# Sheet1_-_mos.net
KiCad netlist of a schematic drawn in Altium Designer
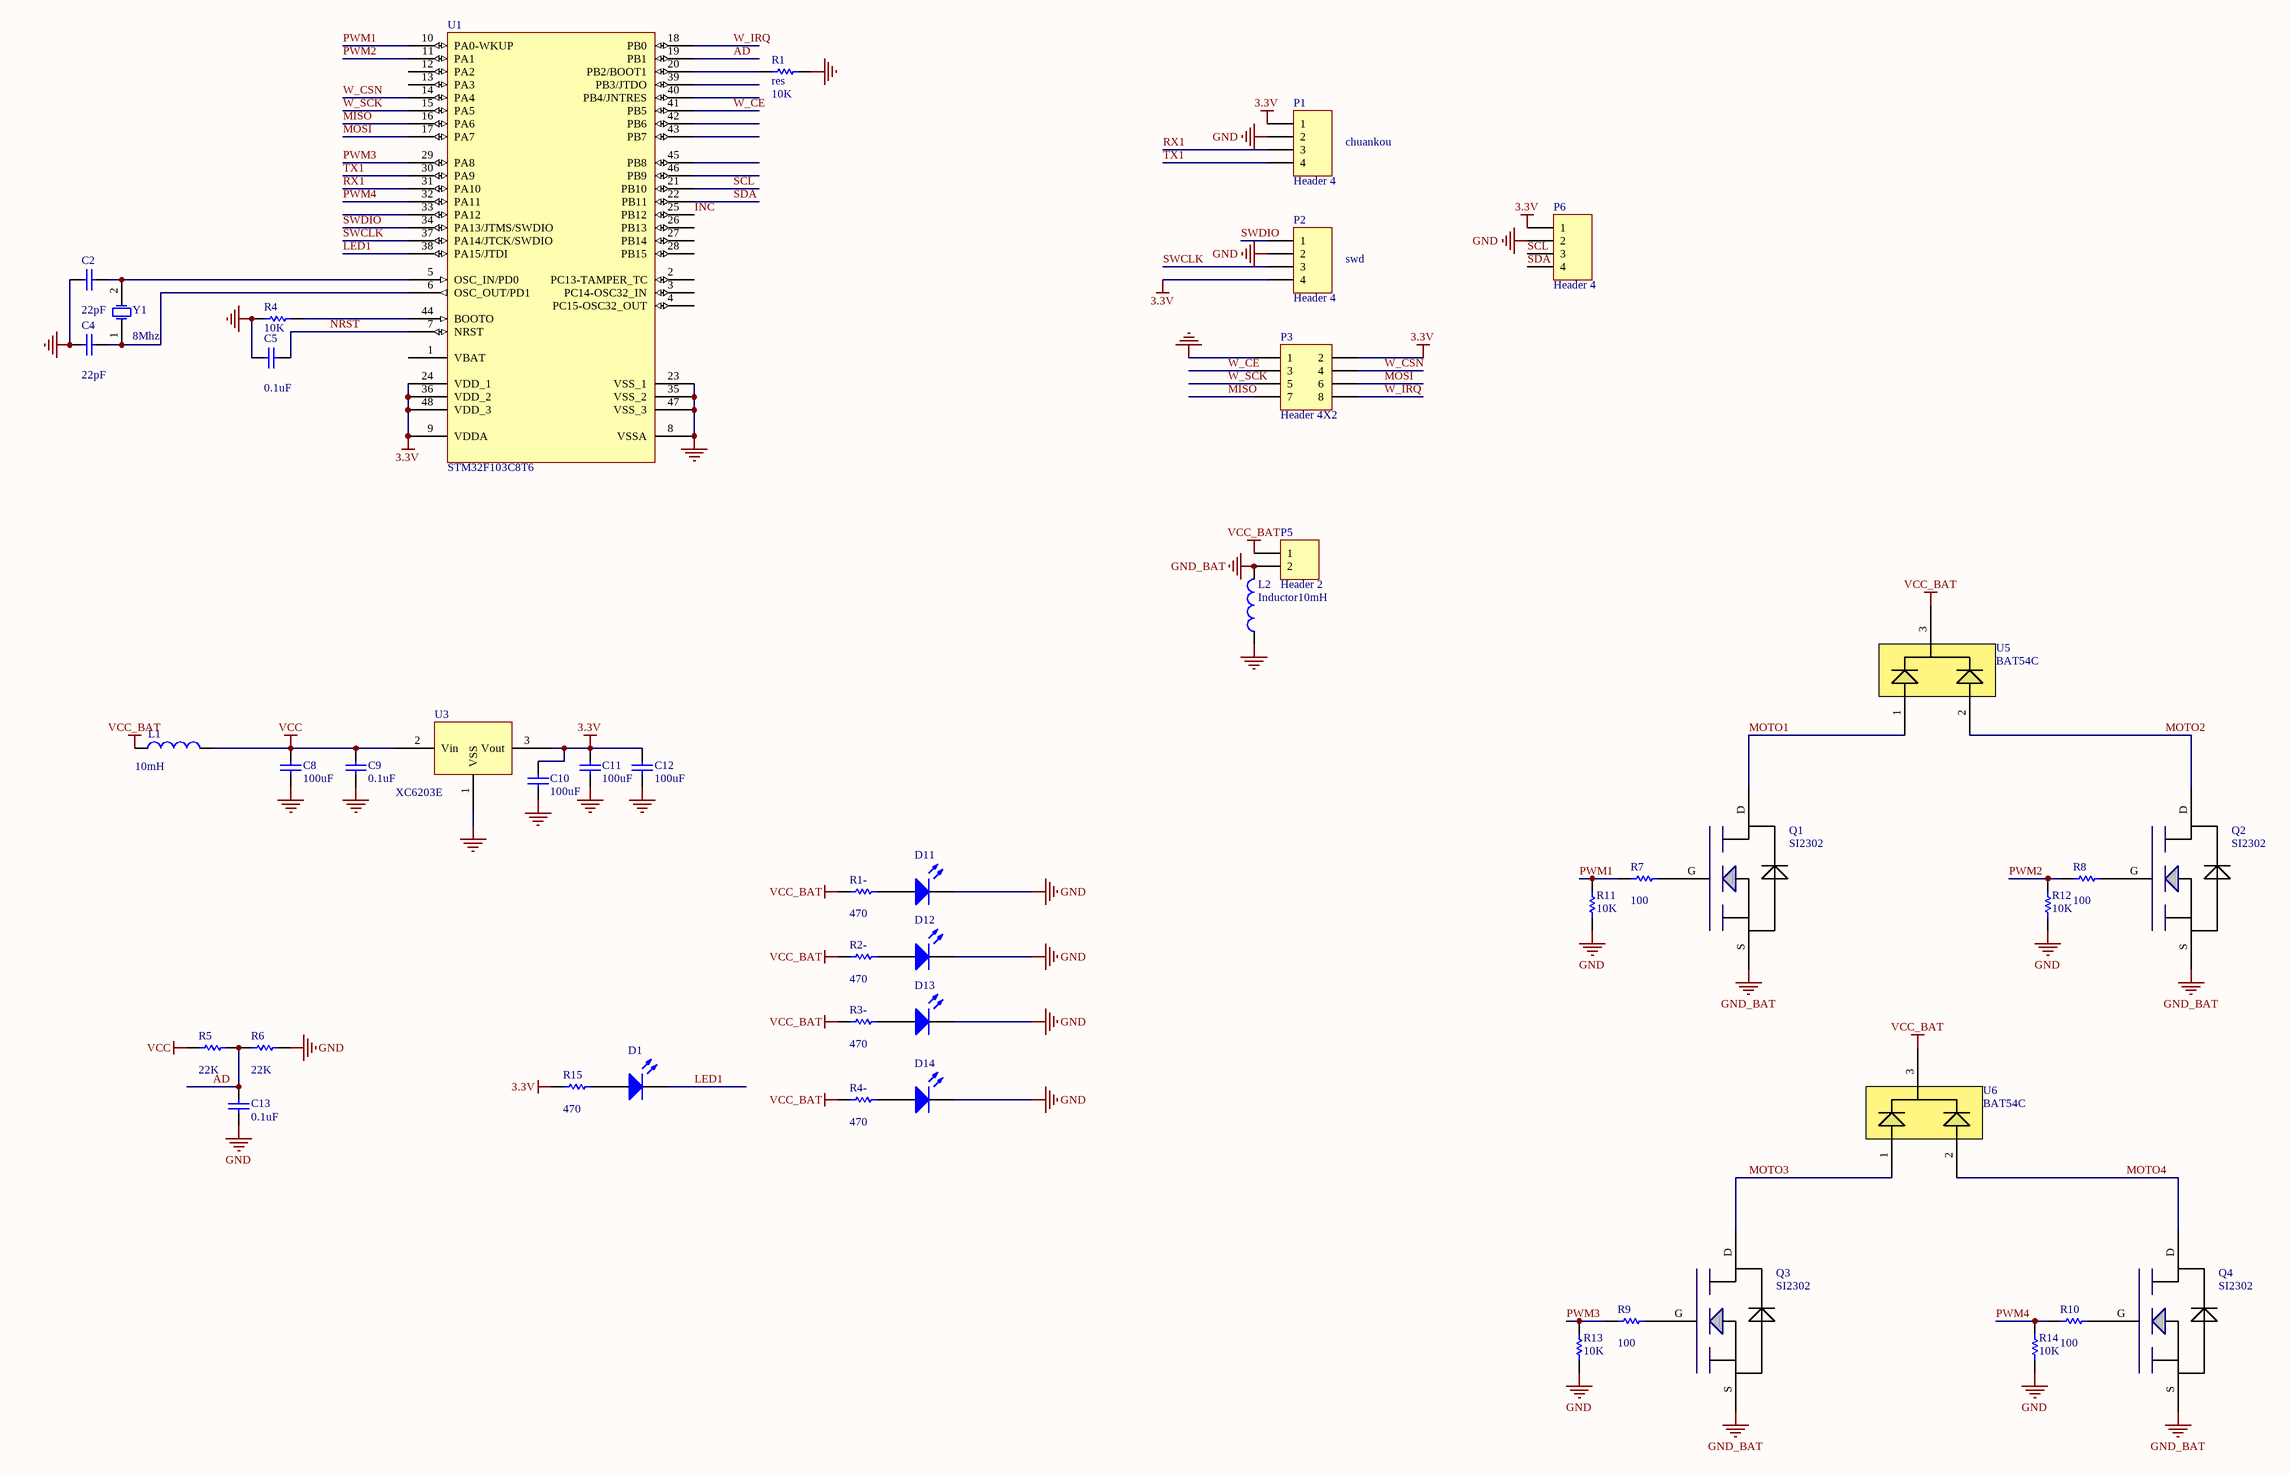
[diagram p0: Sheet1 - 修改mos管.SchDoc]

(export (version "E")
  (design (tool "Eeschema 10.0.6"))
  (components
    (comp (ref "C2")
      (value "22pF")
      (footprint "0603")
      (fields (field (name "Comment") "cap"))
      (libsource (lib "bai") (part "cap"))
    )
    (comp (ref "C4")
      (value "22pF")
      (footprint "0603")
      (fields (field (name "Comment") "cap"))
      (libsource (lib "bai") (part "cap"))
    )
    (comp (ref "C5")
      (value "0.1uF")
      (footprint "0603")
      (fields (field (name "Comment") "cap"))
      (libsource (lib "bai") (part "cap"))
    )
    (comp (ref "C8")
      (value "100uF")
      (footprint "0603")
      (fields (field (name "Comment") "cap"))
      (libsource (lib "bai") (part "cap"))
    )
    (comp (ref "C9")
      (value "0.1uF")
      (footprint "0603")
      (fields (field (name "Comment") "cap"))
      (libsource (lib "bai") (part "cap"))
    )
    (comp (ref "C10")
      (value "100uF")
      (footprint "0603")
      (fields (field (name "Comment") "cap"))
      (libsource (lib "bai") (part "cap"))
    )
    (comp (ref "C11")
      (value "100uF")
      (footprint "0603")
      (fields (field (name "Comment") "cap"))
      (libsource (lib "bai") (part "cap"))
    )
    (comp (ref "C12")
      (value "100uF")
      (footprint "0603")
      (fields (field (name "Comment") "cap"))
      (libsource (lib "bai") (part "cap"))
    )
    (comp (ref "C13")
      (value "0.1uF")
      (footprint "0603")
      (fields (field (name "Comment") "cap"))
      (libsource (lib "bai") (part "cap"))
    )
    (comp (ref "D1")
      (value "LED0")
      (footprint "0805")
      (description "Typical INFRARED GaAs LED")
      (fields (field (name "PUBLISHER") "Altium Limited"))
      (libsource (lib "Miscellaneous Devices") (part "LED0"))
    )
    (comp (ref "D11")
      (value "LED0")
      (footprint "0603c")
      (description "Typical INFRARED GaAs LED")
      (fields (field (name "PUBLISHER") "Altium Limited"))
      (libsource (lib "Miscellaneous Devices") (part "LED0"))
    )
    (comp (ref "D12")
      (value "LED0")
      (footprint "0603c")
      (description "Typical INFRARED GaAs LED")
      (fields (field (name "PUBLISHER") "Altium Limited"))
      (libsource (lib "Miscellaneous Devices") (part "LED0"))
    )
    (comp (ref "D13")
      (value "LED0")
      (footprint "0603c")
      (description "Typical INFRARED GaAs LED")
      (fields (field (name "PUBLISHER") "Altium Limited"))
      (libsource (lib "Miscellaneous Devices") (part "LED0"))
    )
    (comp (ref "D14")
      (value "LED0")
      (footprint "0603c")
      (description "Typical INFRARED GaAs LED")
      (fields (field (name "PUBLISHER") "Altium Limited"))
      (libsource (lib "Miscellaneous Devices") (part "LED0"))
    )
    (comp (ref "L1")
      (value "10mH")
      (footprint "0805")
      (fields (field (name "Comment") "Inductor"))
      (libsource (lib "bai") (part "Inductor"))
    )
    (comp (ref "L2") (value "Inductor10mH") (footprint "0805") (libsource (lib "bai") (part "Inductor")))
    (comp (ref "P1")
      (value "Header 4")
      (footprint "HDR1X4")
      (description "Header, 4-Pin")
      (fields (field (name "PUBLISHER") "Altium Limited"))
      (libsource (lib "Miscellaneous Connectors") (part "Header 4"))
    )
    (comp (ref "P2")
      (value "Header 4")
      (footprint "HDR1X4")
      (description "Header, 4-Pin")
      (fields (field (name "PUBLISHER") "Altium Limited"))
      (libsource (lib "Miscellaneous Connectors") (part "Header 4"))
    )
    (comp (ref "P3")
      (value "Header 4X2")
      (footprint "HDR2X4")
      (description "Header, 4-Pin, Dual row")
      (fields (field (name "PUBLISHER") "Altium Limited"))
      (libsource (lib "Miscellaneous Connectors") (part "Header 4X2"))
    )
    (comp (ref "P5")
      (value "Header 2")
      (footprint "HDR1X2")
      (description "Header, 2-Pin")
      (fields (field (name "PUBLISHER") "Altium Limited"))
      (libsource (lib "Miscellaneous Connectors") (part "Header 2"))
    )
    (comp (ref "P6")
      (value "Header 4")
      (footprint "HDR1X4")
      (description "Header, 4-Pin")
      (fields (field (name "PUBLISHER") "Altium Limited"))
      (libsource (lib "Miscellaneous Connectors") (part "Header 4"))
    )
    (comp (ref "Q1") (value "SI2302") (footprint "SOT-23") (libsource (lib "bai") (part "SI2302")))
    (comp (ref "Q2") (value "SI2302") (footprint "SOT-23") (libsource (lib "bai") (part "SI2302")))
    (comp (ref "Q3") (value "SI2302") (footprint "SOT-23") (libsource (lib "bai") (part "SI2302")))
    (comp (ref "Q4") (value "SI2302") (footprint "SOT-23") (libsource (lib "bai") (part "SI2302")))
    (comp (ref "R1")
      (value "res")
      (footprint "0603")
      (fields (field (name "RES") "10K"))
      (libsource (lib "bai") (part "res"))
    )
    (comp (ref "R1-")
      (value "res")
      (footprint "0603c")
      (fields (field (name "RES") "470"))
      (libsource (lib "bai") (part "res"))
    )
    (comp (ref "R2-")
      (value "res")
      (footprint "0603c")
      (fields (field (name "RES") "470"))
      (libsource (lib "bai") (part "res"))
    )
    (comp (ref "R3-")
      (value "res")
      (footprint "0603c")
      (fields (field (name "RES") "470"))
      (libsource (lib "bai") (part "res"))
    )
    (comp (ref "R4")
      (value "res")
      (footprint "0603")
      (fields (field (name "RES") "10K"))
      (libsource (lib "bai") (part "res"))
    )
    (comp (ref "R4-")
      (value "res")
      (footprint "0603c")
      (fields (field (name "RES") "470"))
      (libsource (lib "bai") (part "res"))
    )
    (comp (ref "R5")
      (value "res")
      (footprint "0603")
      (fields (field (name "RES") "22K"))
      (libsource (lib "bai") (part "res"))
    )
    (comp (ref "R6")
      (value "res")
      (footprint "0603")
      (fields (field (name "RES") "22K"))
      (libsource (lib "bai") (part "res"))
    )
    (comp (ref "R7")
      (value "res")
      (footprint "0603")
      (fields (field (name "RES") "100"))
      (libsource (lib "bai") (part "res"))
    )
    (comp (ref "R8")
      (value "res")
      (footprint "0603")
      (fields (field (name "RES") "100"))
      (libsource (lib "bai") (part "res"))
    )
    (comp (ref "R9")
      (value "res")
      (footprint "0603")
      (fields (field (name "RES") "100"))
      (libsource (lib "bai") (part "res"))
    )
    (comp (ref "R10")
      (value "res")
      (footprint "0603")
      (fields (field (name "RES") "100"))
      (libsource (lib "bai") (part "res"))
    )
    (comp (ref "R11")
      (value "res")
      (footprint "0603")
      (fields (field (name "RES") "10K"))
      (libsource (lib "bai") (part "res"))
    )
    (comp (ref "R12")
      (value "res")
      (footprint "0603")
      (fields (field (name "RES") "10K"))
      (libsource (lib "bai") (part "res"))
    )
    (comp (ref "R13")
      (value "res")
      (footprint "0603")
      (fields (field (name "RES") "10K"))
      (libsource (lib "bai") (part "res"))
    )
    (comp (ref "R14")
      (value "res")
      (footprint "0603")
      (fields (field (name "RES") "10K"))
      (libsource (lib "bai") (part "res"))
    )
    (comp (ref "R15")
      (value "res")
      (footprint "0603")
      (fields (field (name "RES") "470"))
      (libsource (lib "bai") (part "res"))
    )
    (comp (ref "U1")
      (value "STM32F103C8T6")
      (footprint "LQFP48S")
      (libsource (lib "bai") (part "STM32F103C8T6"))
    )
    (comp (ref "U3") (value "XC6203E") (footprint "SOT-89") (libsource (lib "文哥做的") (part "XC6203")))
    (comp (ref "U5") (value "BAT54C") (footprint "SOT-23") (libsource (lib "bai") (part "BAT54C")))
    (comp (ref "U6") (value "BAT54C") (footprint "SOT-23") (libsource (lib "bai") (part "BAT54C")))
    (comp (ref "Y1")
      (value "5032xtal")
      (footprint "XTAL")
      (fields (field (name "ALTIUM_UNNAMED_1") "8Mhz"))
      (libsource (lib "bai") (part "5032xtal"))
    )
  )
  (nets
    (net (code "1") (name "/AD") (class "Default")
      (node (ref "C13") (pin "2") (pinfunction "2_2") (pintype "passive"))
      (node (ref "R5") (pin "2") (pinfunction "2_2") (pintype "passive"))
      (node (ref "R6") (pin "1") (pinfunction "1_1") (pintype "passive"))
      (node (ref "U1") (pin "19") (pinfunction "PB1_19") (pintype "bidirectional"))
    )
    (net (code "2") (name "/INC") (class "Default")
      (node (ref "U1") (pin "25") (pinfunction "PB12_25") (pintype "bidirectional"))
    )
    (net (code "3") (name "/LED1") (class "Default")
      (node (ref "D1") (pin "2") (pinfunction "K_2") (pintype "passive"))
      (node (ref "U1") (pin "38") (pinfunction "PA15/JTDI_38") (pintype "bidirectional"))
    )
    (net (code "4") (name "/MISO") (class "Default")
      (node (ref "P3") (pin "7") (pinfunction "7_7") (pintype "passive"))
      (node (ref "U1") (pin "16") (pinfunction "PA6_16") (pintype "bidirectional"))
    )
    (net (code "5") (name "/MOSI") (class "Default")
      (node (ref "P3") (pin "6") (pinfunction "6_6") (pintype "passive"))
      (node (ref "U1") (pin "17") (pinfunction "PA7_17") (pintype "bidirectional"))
    )
    (net (code "6") (name "/MOTO1") (class "Default")
      (node (ref "Q1") (pin "D") (pinfunction "3_D") (pintype "passive"))
      (node (ref "U5") (pin "1") (pinfunction "4_1") (pintype "passive"))
    )
    (net (code "7") (name "/MOTO2") (class "Default")
      (node (ref "Q2") (pin "D") (pinfunction "3_D") (pintype "passive"))
      (node (ref "U5") (pin "2") (pinfunction "5_2") (pintype "passive"))
    )
    (net (code "8") (name "/MOTO3") (class "Default")
      (node (ref "Q3") (pin "D") (pinfunction "3_D") (pintype "passive"))
      (node (ref "U6") (pin "1") (pinfunction "4_1") (pintype "passive"))
    )
    (net (code "9") (name "/MOTO4") (class "Default")
      (node (ref "Q4") (pin "D") (pinfunction "3_D") (pintype "passive"))
      (node (ref "U6") (pin "2") (pinfunction "5_2") (pintype "passive"))
    )
    (net (code "10") (name "/NRST") (class "Default")
      (node (ref "C5") (pin "2") (pinfunction "2_2") (pintype "passive"))
      (node (ref "U1") (pin "7") (pinfunction "NRST_7") (pintype "bidirectional"))
    )
    (net (code "11") (name "/PWM1") (class "Default")
      (node (ref "R11") (pin "2") (pinfunction "2_2") (pintype "passive"))
      (node (ref "R7") (pin "1") (pinfunction "1_1") (pintype "passive"))
      (node (ref "U1") (pin "10") (pinfunction "PA0-WKUP_10") (pintype "bidirectional"))
    )
    (net (code "12") (name "/PWM2") (class "Default")
      (node (ref "R12") (pin "2") (pinfunction "2_2") (pintype "passive"))
      (node (ref "R8") (pin "1") (pinfunction "1_1") (pintype "passive"))
      (node (ref "U1") (pin "11") (pinfunction "PA1_11") (pintype "bidirectional"))
    )
    (net (code "13") (name "/PWM3") (class "Default")
      (node (ref "R13") (pin "2") (pinfunction "2_2") (pintype "passive"))
      (node (ref "R9") (pin "1") (pinfunction "1_1") (pintype "passive"))
      (node (ref "U1") (pin "29") (pinfunction "PA8_29") (pintype "bidirectional"))
    )
    (net (code "14") (name "/PWM4") (class "Default")
      (node (ref "R10") (pin "1") (pinfunction "1_1") (pintype "passive"))
      (node (ref "R14") (pin "2") (pinfunction "2_2") (pintype "passive"))
      (node (ref "U1") (pin "32") (pinfunction "PA11_32") (pintype "bidirectional"))
    )
    (net (code "15") (name "/RX1") (class "Default")
      (node (ref "P1") (pin "3") (pinfunction "3_3") (pintype "passive"))
      (node (ref "U1") (pin "31") (pinfunction "PA10_31") (pintype "bidirectional"))
    )
    (net (code "16") (name "/SCL") (class "Default")
      (node (ref "P6") (pin "3") (pinfunction "3_3") (pintype "passive"))
      (node (ref "U1") (pin "21") (pinfunction "PB10_21") (pintype "bidirectional"))
    )
    (net (code "17") (name "/SDA") (class "Default")
      (node (ref "P6") (pin "4") (pinfunction "4_4") (pintype "passive"))
      (node (ref "U1") (pin "22") (pinfunction "PB11_22") (pintype "bidirectional"))
    )
    (net (code "18") (name "/SWCLK") (class "Default")
      (node (ref "P2") (pin "3") (pinfunction "3_3") (pintype "passive"))
      (node (ref "U1") (pin "37") (pinfunction "PA14/JTCK/SWDIO_37") (pintype "bidirectional"))
    )
    (net (code "19") (name "/SWDIO") (class "Default")
      (node (ref "P2") (pin "1") (pinfunction "1_1") (pintype "passive"))
      (node (ref "U1") (pin "34") (pinfunction "PA13/JTMS/SWDIO_34") (pintype "bidirectional"))
    )
    (net (code "20") (name "/TX1") (class "Default")
      (node (ref "P1") (pin "4") (pinfunction "4_4") (pintype "passive"))
      (node (ref "U1") (pin "30") (pinfunction "PA9_30") (pintype "bidirectional"))
    )
    (net (code "21") (name "/W_CE") (class "Default")
      (node (ref "P3") (pin "3") (pinfunction "3_3") (pintype "passive"))
      (node (ref "U1") (pin "41") (pinfunction "PB5_41") (pintype "bidirectional"))
    )
    (net (code "22") (name "/W_CSN") (class "Default")
      (node (ref "P3") (pin "4") (pinfunction "4_4") (pintype "passive"))
      (node (ref "U1") (pin "14") (pinfunction "PA4_14") (pintype "bidirectional"))
    )
    (net (code "23") (name "/W_IRQ") (class "Default")
      (node (ref "P3") (pin "8") (pinfunction "8_8") (pintype "passive"))
      (node (ref "U1") (pin "18") (pinfunction "PB0_18") (pintype "bidirectional"))
    )
    (net (code "24") (name "/W_SCK") (class "Default")
      (node (ref "P3") (pin "5") (pinfunction "5_5") (pintype "passive"))
      (node (ref "U1") (pin "15") (pinfunction "PA5_15") (pintype "bidirectional"))
    )
    (net (code "25") (name "3.3V") (class "Default")
      (node (ref "C10") (pin "2") (pinfunction "2_2") (pintype "passive"))
      (node (ref "C11") (pin "2") (pinfunction "2_2") (pintype "passive"))
      (node (ref "C12") (pin "2") (pinfunction "2_2") (pintype "passive"))
      (node (ref "P1") (pin "1") (pinfunction "1_1") (pintype "passive"))
      (node (ref "P2") (pin "4") (pinfunction "4_4") (pintype "passive"))
      (node (ref "P3") (pin "2") (pinfunction "2_2") (pintype "passive"))
      (node (ref "P6") (pin "1") (pinfunction "1_1") (pintype "passive"))
      (node (ref "R15") (pin "1") (pinfunction "1_1") (pintype "passive"))
      (node (ref "U1") (pin "24") (pinfunction "VDD_1_24") (pintype "passive"))
      (node (ref "U1") (pin "36") (pinfunction "VDD_2_36") (pintype "passive"))
      (node (ref "U1") (pin "48") (pinfunction "VDD_3_48") (pintype "passive"))
      (node (ref "U1") (pin "9") (pinfunction "VDDA_9") (pintype "passive"))
      (node (ref "U3") (pin "3") (pinfunction "Vout_3") (pintype "passive"))
    )
    (net (code "26") (name "GND") (class "Default")
      (node (ref "C10") (pin "1") (pinfunction "1_1") (pintype "passive"))
      (node (ref "C11") (pin "1") (pinfunction "1_1") (pintype "passive"))
      (node (ref "C12") (pin "1") (pinfunction "1_1") (pintype "passive"))
      (node (ref "C13") (pin "1") (pinfunction "1_1") (pintype "passive"))
      (node (ref "C2") (pin "1") (pinfunction "1_1") (pintype "passive"))
      (node (ref "C4") (pin "1") (pinfunction "1_1") (pintype "passive"))
      (node (ref "C5") (pin "1") (pinfunction "1_1") (pintype "passive"))
      (node (ref "C8") (pin "1") (pinfunction "1_1") (pintype "passive"))
      (node (ref "C9") (pin "1") (pinfunction "1_1") (pintype "passive"))
      (node (ref "D11") (pin "2") (pinfunction "K_2") (pintype "passive"))
      (node (ref "D12") (pin "2") (pinfunction "K_2") (pintype "passive"))
      (node (ref "D13") (pin "2") (pinfunction "K_2") (pintype "passive"))
      (node (ref "D14") (pin "2") (pinfunction "K_2") (pintype "passive"))
      (node (ref "L2") (pin "1") (pinfunction "1_1") (pintype "passive"))
      (node (ref "P1") (pin "2") (pinfunction "2_2") (pintype "passive"))
      (node (ref "P2") (pin "2") (pinfunction "2_2") (pintype "passive"))
      (node (ref "P3") (pin "1") (pinfunction "1_1") (pintype "passive"))
      (node (ref "P6") (pin "2") (pinfunction "2_2") (pintype "passive"))
      (node (ref "R1") (pin "2") (pinfunction "2_2") (pintype "passive"))
      (node (ref "R11") (pin "1") (pinfunction "1_1") (pintype "passive"))
      (node (ref "R12") (pin "1") (pinfunction "1_1") (pintype "passive"))
      (node (ref "R13") (pin "1") (pinfunction "1_1") (pintype "passive"))
      (node (ref "R14") (pin "1") (pinfunction "1_1") (pintype "passive"))
      (node (ref "R4") (pin "1") (pinfunction "1_1") (pintype "passive"))
      (node (ref "R6") (pin "2") (pinfunction "2_2") (pintype "passive"))
      (node (ref "U1") (pin "23") (pinfunction "VSS_1_23") (pintype "passive"))
      (node (ref "U1") (pin "35") (pinfunction "VSS_2_35") (pintype "passive"))
      (node (ref "U1") (pin "47") (pinfunction "VSS_3_47") (pintype "passive"))
      (node (ref "U1") (pin "8") (pinfunction "VSSA_8") (pintype "passive"))
      (node (ref "U3") (pin "1") (pinfunction "VSS_1") (pintype "passive"))
    )
    (net (code "27") (name "GND_BAT") (class "Default")
      (node (ref "L2") (pin "2") (pinfunction "2_2") (pintype "passive"))
      (node (ref "P5") (pin "2") (pinfunction "2_2") (pintype "passive"))
      (node (ref "Q1") (pin "S") (pinfunction "2_S") (pintype "passive"))
      (node (ref "Q2") (pin "S") (pinfunction "2_S") (pintype "passive"))
      (node (ref "Q3") (pin "S") (pinfunction "2_S") (pintype "passive"))
      (node (ref "Q4") (pin "S") (pinfunction "2_S") (pintype "passive"))
    )
    (net (code "28") (name "Net-(D1-A)") (class "Default")
      (node (ref "D1") (pin "1") (pinfunction "A_1") (pintype "passive"))
      (node (ref "R15") (pin "2") (pinfunction "2_2") (pintype "passive"))
    )
    (net (code "29") (name "Net-(D11-A)") (class "Default")
      (node (ref "D11") (pin "1") (pinfunction "A_1") (pintype "passive"))
      (node (ref "R1-") (pin "2") (pinfunction "2_2") (pintype "passive"))
    )
    (net (code "30") (name "Net-(D12-A)") (class "Default")
      (node (ref "D12") (pin "1") (pinfunction "A_1") (pintype "passive"))
      (node (ref "R2-") (pin "2") (pinfunction "2_2") (pintype "passive"))
    )
    (net (code "31") (name "Net-(D13-A)") (class "Default")
      (node (ref "D13") (pin "1") (pinfunction "A_1") (pintype "passive"))
      (node (ref "R3-") (pin "2") (pinfunction "2_2") (pintype "passive"))
    )
    (net (code "32") (name "Net-(D14-A)") (class "Default")
      (node (ref "D14") (pin "1") (pinfunction "A_1") (pintype "passive"))
      (node (ref "R4-") (pin "2") (pinfunction "2_2") (pintype "passive"))
    )
    (net (code "33") (name "Net-(Q1-PadG)") (class "Default")
      (node (ref "Q1") (pin "G") (pinfunction "G_G") (pintype "passive"))
      (node (ref "R7") (pin "2") (pinfunction "2_2") (pintype "passive"))
    )
    (net (code "34") (name "Net-(Q2-PadG)") (class "Default")
      (node (ref "Q2") (pin "G") (pinfunction "G_G") (pintype "passive"))
      (node (ref "R8") (pin "2") (pinfunction "2_2") (pintype "passive"))
    )
    (net (code "35") (name "Net-(Q3-PadG)") (class "Default")
      (node (ref "Q3") (pin "G") (pinfunction "G_G") (pintype "passive"))
      (node (ref "R9") (pin "2") (pinfunction "2_2") (pintype "passive"))
    )
    (net (code "36") (name "Net-(Q4-PadG)") (class "Default")
      (node (ref "Q4") (pin "G") (pinfunction "G_G") (pintype "passive"))
      (node (ref "R10") (pin "2") (pinfunction "2_2") (pintype "passive"))
    )
    (net (code "37") (name "Net-(U1-BOOTO)") (class "Default")
      (node (ref "R4") (pin "2") (pinfunction "2_2") (pintype "passive"))
      (node (ref "U1") (pin "44") (pinfunction "BOOTO_44") (pintype "input"))
    )
    (net (code "38") (name "Net-(U1-OSC_IN{slash}PD0)") (class "Default")
      (node (ref "C2") (pin "2") (pinfunction "2_2") (pintype "passive"))
      (node (ref "U1") (pin "5") (pinfunction "OSC_IN/PD0_5") (pintype "input"))
      (node (ref "Y1") (pin "2") (pinfunction "OSC2_2") (pintype "passive"))
    )
    (net (code "39") (name "Net-(U1-OSC_OUT{slash}PD1)") (class "Default")
      (node (ref "C4") (pin "2") (pinfunction "2_2") (pintype "passive"))
      (node (ref "U1") (pin "6") (pinfunction "OSC_OUT/PD1_6") (pintype "output"))
      (node (ref "Y1") (pin "1") (pinfunction "OSC1_1") (pintype "passive"))
    )
    (net (code "40") (name "Net-(U1-PB2{slash}BOOT1)") (class "Default")
      (node (ref "R1") (pin "1") (pinfunction "1_1") (pintype "passive"))
      (node (ref "U1") (pin "20") (pinfunction "PB2/BOOT1_20") (pintype "bidirectional"))
    )
    (net (code "41") (name "VCC") (class "Default")
      (node (ref "C8") (pin "2") (pinfunction "2_2") (pintype "passive"))
      (node (ref "C9") (pin "2") (pinfunction "2_2") (pintype "passive"))
      (node (ref "L1") (pin "2") (pinfunction "2_2") (pintype "passive"))
      (node (ref "R5") (pin "1") (pinfunction "1_1") (pintype "passive"))
      (node (ref "U3") (pin "2") (pinfunction "Vin_2") (pintype "passive"))
    )
    (net (code "42") (name "VCC_BAT") (class "Default")
      (node (ref "L1") (pin "1") (pinfunction "1_1") (pintype "passive"))
      (node (ref "P5") (pin "1") (pinfunction "1_1") (pintype "passive"))
      (node (ref "R1-") (pin "1") (pinfunction "1_1") (pintype "passive"))
      (node (ref "R2-") (pin "1") (pinfunction "1_1") (pintype "passive"))
      (node (ref "R3-") (pin "1") (pinfunction "1_1") (pintype "passive"))
      (node (ref "R4-") (pin "1") (pinfunction "1_1") (pintype "passive"))
      (node (ref "U5") (pin "3") (pinfunction "0_3") (pintype "passive"))
      (node (ref "U6") (pin "3") (pinfunction "0_3") (pintype "passive"))
    )
    (net (code "43") (name "unconnected-(U1-PA2-Pad12)") (class "Default")
      (node (ref "U1") (pin "12") (pinfunction "PA2_12") (pintype "bidirectional"))
    )
    (net (code "44") (name "unconnected-(U1-PA3-Pad13)") (class "Default")
      (node (ref "U1") (pin "13") (pinfunction "PA3_13") (pintype "bidirectional"))
    )
    (net (code "45") (name "unconnected-(U1-PA12-Pad33)") (class "Default")
      (node (ref "U1") (pin "33") (pinfunction "PA12_33") (pintype "bidirectional"))
    )
    (net (code "46") (name "unconnected-(U1-PB3{slash}JTDO-Pad39)") (class "Default")
      (node (ref "U1") (pin "39") (pinfunction "PB3/JTDO_39") (pintype "bidirectional"))
    )
    (net (code "47") (name "unconnected-(U1-PB4{slash}JNTRES-Pad40)") (class "Default")
      (node (ref "U1") (pin "40") (pinfunction "PB4/JNTRES_40") (pintype "bidirectional"))
    )
    (net (code "48") (name "unconnected-(U1-PB6-Pad42)") (class "Default")
      (node (ref "U1") (pin "42") (pinfunction "PB6_42") (pintype "bidirectional"))
    )
    (net (code "49") (name "unconnected-(U1-PB7-Pad43)") (class "Default")
      (node (ref "U1") (pin "43") (pinfunction "PB7_43") (pintype "bidirectional"))
    )
    (net (code "50") (name "unconnected-(U1-PB8-Pad45)") (class "Default")
      (node (ref "U1") (pin "45") (pinfunction "PB8_45") (pintype "bidirectional"))
    )
    (net (code "51") (name "unconnected-(U1-PB9-Pad46)") (class "Default")
      (node (ref "U1") (pin "46") (pinfunction "PB9_46") (pintype "bidirectional"))
    )
    (net (code "52") (name "unconnected-(U1-PB13-Pad26)") (class "Default")
      (node (ref "U1") (pin "26") (pinfunction "PB13_26") (pintype "bidirectional"))
    )
    (net (code "53") (name "unconnected-(U1-PB14-Pad27)") (class "Default")
      (node (ref "U1") (pin "27") (pinfunction "PB14_27") (pintype "bidirectional"))
    )
    (net (code "54") (name "unconnected-(U1-PB15-Pad28)") (class "Default")
      (node (ref "U1") (pin "28") (pinfunction "PB15_28") (pintype "bidirectional"))
    )
    (net (code "55") (name "unconnected-(U1-PC13-TAMPER_TC-Pad2)") (class "Default")
      (node (ref "U1") (pin "2") (pinfunction "PC13-TAMPER_TC_2") (pintype "bidirectional"))
    )
    (net (code "56") (name "unconnected-(U1-PC14-OSC32_IN-Pad3)") (class "Default")
      (node (ref "U1") (pin "3") (pinfunction "PC14-OSC32_IN_3") (pintype "bidirectional"))
    )
    (net (code "57") (name "unconnected-(U1-PC15-OSC32_OUT-Pad4)") (class "Default")
      (node (ref "U1") (pin "4") (pinfunction "PC15-OSC32_OUT_4") (pintype "bidirectional"))
    )
    (net (code "58") (name "unconnected-(U1-VBAT-Pad1)") (class "Default")
      (node (ref "U1") (pin "1") (pinfunction "VBAT_1") (pintype "passive"))
    )
  )
)
